# StormNet18-Remote-v0_1.net
KiCad netlist of a schematic drawn in EAGLE
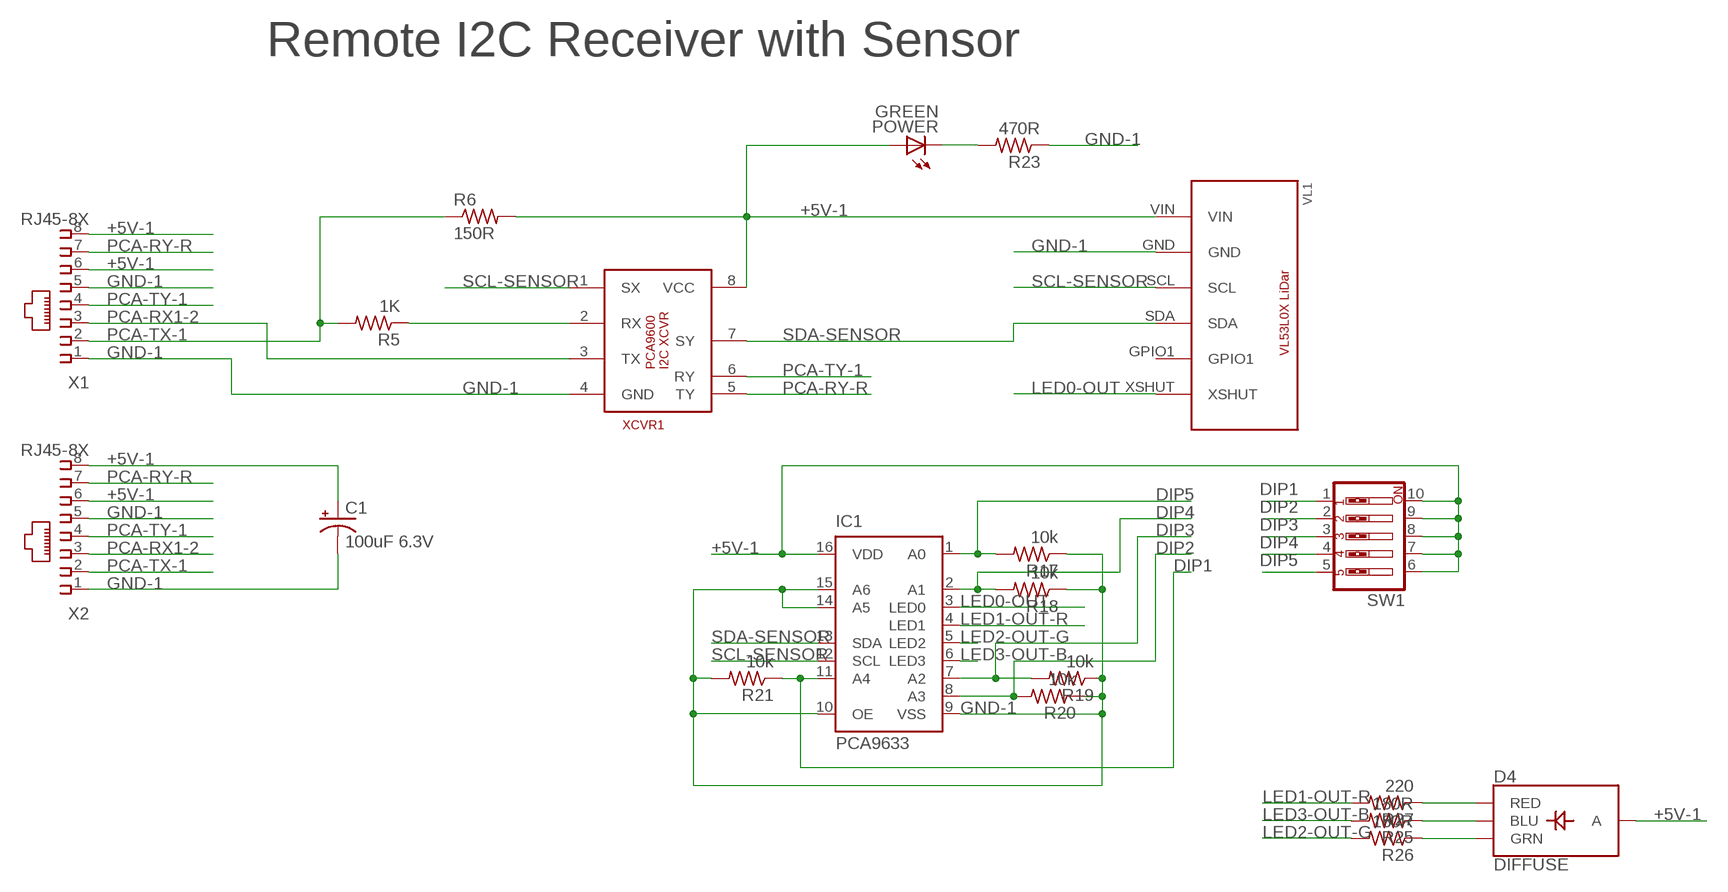
[diagram p0: schematic, sheet 1]

(export (version "E")
  (design (tool "Eeschema 10.0.6"))
  (components
    (comp (ref "C1")
      (value "100uF 6.3V")
      (footprint "eagle-import:CT3528")
      (libsource (lib "eagle-import") (part "CPOL-USCT3528"))
    )
    (comp (ref "D4")
      (value "DIFFUSE")
      (footprint "eagle-import:LED-RGB-THRU")
      (libsource (lib "eagle-import") (part "LED-RGB-CADIFFUSE"))
    )
    (comp (ref "IC1")
      (value "PCA9633")
      (footprint "eagle-import:SO16")
      (libsource (lib "eagle-import") (part "PCA9633"))
    )
    (comp (ref "POWER")
      (value "GREEN")
      (footprint "eagle-import:CHIPLED_1206")
      (libsource (lib "eagle-import") (part "LEDCHIPLED_1206"))
    )
    (comp (ref "R5")
      (value "1K")
      (footprint "eagle-import:R0603")
      (libsource (lib "eagle-import") (part "R-US_R0603"))
    )
    (comp (ref "R6")
      (value "150R")
      (footprint "eagle-import:R0603")
      (libsource (lib "eagle-import") (part "R-US_R0603"))
    )
    (comp (ref "R17")
      (value "10k")
      (footprint "eagle-import:R0603")
      (libsource (lib "eagle-import") (part "R-US_R0603"))
    )
    (comp (ref "R18")
      (value "10k")
      (footprint "eagle-import:R0603")
      (libsource (lib "eagle-import") (part "R-US_R0603"))
    )
    (comp (ref "R19")
      (value "10k")
      (footprint "eagle-import:R0603")
      (libsource (lib "eagle-import") (part "R-US_R0603"))
    )
    (comp (ref "R20")
      (value "10k")
      (footprint "eagle-import:R0603")
      (libsource (lib "eagle-import") (part "R-US_R0603"))
    )
    (comp (ref "R21")
      (value "10k")
      (footprint "eagle-import:R0603")
      (libsource (lib "eagle-import") (part "R-US_R0603"))
    )
    (comp (ref "R23")
      (value "470R")
      (footprint "eagle-import:R0603")
      (libsource (lib "eagle-import") (part "R-US_R0603"))
    )
    (comp (ref "R25")
      (value "180R")
      (footprint "eagle-import:R0603")
      (libsource (lib "eagle-import") (part "R-US_R0603"))
    )
    (comp (ref "R26")
      (value "180R")
      (footprint "eagle-import:R0603")
      (libsource (lib "eagle-import") (part "R-US_R0603"))
    )
    (comp (ref "R27")
      (value "220")
      (footprint "eagle-import:R0603")
      (libsource (lib "eagle-import") (part "R-US_R0603"))
    )
    (comp (ref "SW1")
      (value "SW_DIP-5")
      (footprint "eagle-import:EDG-05")
      (libsource (lib "eagle-import") (part "SW_DIP-5"))
    )
    (comp (ref "VL1")
      (value "VL53L0X-GREEN")
      (footprint "eagle-import:VL53L0X-GREEN")
      (libsource (lib "eagle-import") (part "VL53L0X-GREEN"))
    )
    (comp (ref "X1")
      (value "RJ45-8X")
      (footprint "eagle-import:RJ45-NO-SHIELD")
      (libsource (lib "eagle-import") (part "RJ45-8X"))
    )
    (comp (ref "X2")
      (value "RJ45-8X")
      (footprint "eagle-import:RJ45-NO-SHIELD")
      (libsource (lib "eagle-import") (part "RJ45-8X"))
    )
    (comp (ref "XCVR1")
      (value "PCA9600DSO8")
      (footprint "eagle-import:SO08")
      (libsource (lib "eagle-import") (part "PCA9600DSO8"))
    )
  )
  (nets
    (net (code "1") (name "/+5V-1") (class "Default")
      (node (ref "C1") (pin "+") (pinfunction "+_+") (pintype "passive"))
      (node (ref "D4") (pin "2") (pinfunction "A_2") (pintype "bidirectional"))
      (node (ref "IC1") (pin "16") (pinfunction "VDD_16") (pintype "power_in"))
      (node (ref "POWER") (pin "A") (pinfunction "A_A") (pintype "passive"))
      (node (ref "R6") (pin "2") (pinfunction "2_2") (pintype "passive"))
      (node (ref "SW1") (pin "10") (pinfunction "10_10") (pintype "passive"))
      (node (ref "SW1") (pin "6") (pinfunction "6_6") (pintype "passive"))
      (node (ref "SW1") (pin "7") (pinfunction "7_7") (pintype "passive"))
      (node (ref "SW1") (pin "8") (pinfunction "8_8") (pintype "passive"))
      (node (ref "SW1") (pin "9") (pinfunction "9_9") (pintype "passive"))
      (node (ref "VL1") (pin "VIN") (pinfunction "VIN_VIN") (pintype "power_in"))
      (node (ref "X1") (pin "6") (pinfunction "6_6") (pintype "passive"))
      (node (ref "X1") (pin "8") (pinfunction "8_8") (pintype "passive"))
      (node (ref "X2") (pin "6") (pinfunction "6_6") (pintype "passive"))
      (node (ref "X2") (pin "8") (pinfunction "8_8") (pintype "passive"))
      (node (ref "XCVR1") (pin "8") (pinfunction "VCC_8") (pintype "bidirectional"))
    )
    (net (code "2") (name "/DIP1") (class "Default")
      (node (ref "IC1") (pin "11") (pinfunction "A4_11") (pintype "input"))
      (node (ref "R21") (pin "1") (pinfunction "1_1") (pintype "passive"))
      (node (ref "SW1") (pin "1") (pinfunction "1_1") (pintype "passive"))
    )
    (net (code "3") (name "/DIP2") (class "Default")
      (node (ref "IC1") (pin "8") (pinfunction "A3_8") (pintype "bidirectional"))
      (node (ref "R20") (pin "2") (pinfunction "2_2") (pintype "passive"))
      (node (ref "SW1") (pin "2") (pinfunction "2_2") (pintype "passive"))
    )
    (net (code "4") (name "/DIP3") (class "Default")
      (node (ref "IC1") (pin "7") (pinfunction "A2_7") (pintype "bidirectional"))
      (node (ref "R19") (pin "2") (pinfunction "2_2") (pintype "passive"))
      (node (ref "SW1") (pin "3") (pinfunction "3_3") (pintype "passive"))
    )
    (net (code "5") (name "/DIP4") (class "Default")
      (node (ref "IC1") (pin "2") (pinfunction "A1_2") (pintype "bidirectional"))
      (node (ref "R18") (pin "2") (pinfunction "2_2") (pintype "passive"))
      (node (ref "SW1") (pin "4") (pinfunction "4_4") (pintype "passive"))
    )
    (net (code "6") (name "/DIP5") (class "Default")
      (node (ref "IC1") (pin "1") (pinfunction "A0_1") (pintype "open_collector"))
      (node (ref "R17") (pin "2") (pinfunction "2_2") (pintype "passive"))
      (node (ref "SW1") (pin "5") (pinfunction "5_5") (pintype "passive"))
    )
    (net (code "7") (name "/GND-1") (class "Default")
      (node (ref "C1") (pin "-") (pinfunction "-_-") (pintype "passive"))
      (node (ref "IC1") (pin "10") (pinfunction "OE_10") (pintype "power_in"))
      (node (ref "IC1") (pin "14") (pinfunction "A5_14") (pintype "bidirectional"))
      (node (ref "IC1") (pin "15") (pinfunction "A6_15") (pintype "input"))
      (node (ref "IC1") (pin "9") (pinfunction "VSS_9") (pintype "bidirectional"))
      (node (ref "R17") (pin "1") (pinfunction "1_1") (pintype "passive"))
      (node (ref "R18") (pin "1") (pinfunction "1_1") (pintype "passive"))
      (node (ref "R19") (pin "1") (pinfunction "1_1") (pintype "passive"))
      (node (ref "R20") (pin "1") (pinfunction "1_1") (pintype "passive"))
      (node (ref "R21") (pin "2") (pinfunction "2_2") (pintype "passive"))
      (node (ref "R23") (pin "1") (pinfunction "1_1") (pintype "passive"))
      (node (ref "VL1") (pin "GND") (pinfunction "GND_GND") (pintype "power_in"))
      (node (ref "X1") (pin "1") (pinfunction "1_1") (pintype "passive"))
      (node (ref "X1") (pin "5") (pinfunction "5_5") (pintype "passive"))
      (node (ref "X2") (pin "1") (pinfunction "1_1") (pintype "passive"))
      (node (ref "X2") (pin "5") (pinfunction "5_5") (pintype "passive"))
      (node (ref "XCVR1") (pin "4") (pinfunction "GND_4") (pintype "bidirectional"))
    )
    (net (code "8") (name "/LED0-OUT") (class "Default")
      (node (ref "IC1") (pin "3") (pinfunction "LED0_3") (pintype "bidirectional"))
      (node (ref "VL1") (pin "XSHUT") (pinfunction "XSHUT_XSHUT") (pintype "input"))
    )
    (net (code "9") (name "/LED1-OUT-R") (class "Default")
      (node (ref "IC1") (pin "4") (pinfunction "LED1_4") (pintype "bidirectional"))
      (node (ref "R27") (pin "2") (pinfunction "2_2") (pintype "passive"))
    )
    (net (code "10") (name "/LED2-OUT-G") (class "Default")
      (node (ref "IC1") (pin "5") (pinfunction "LED2_5") (pintype "bidirectional"))
      (node (ref "R26") (pin "2") (pinfunction "2_2") (pintype "passive"))
    )
    (net (code "11") (name "/LED3-OUT-B") (class "Default")
      (node (ref "IC1") (pin "6") (pinfunction "LED3_6") (pintype "bidirectional"))
      (node (ref "R25") (pin "2") (pinfunction "2_2") (pintype "passive"))
    )
    (net (code "12") (name "/PCA-RX1-2") (class "Default")
      (node (ref "X1") (pin "3") (pinfunction "3_3") (pintype "passive"))
      (node (ref "X2") (pin "3") (pinfunction "3_3") (pintype "passive"))
      (node (ref "XCVR1") (pin "3") (pinfunction "TX_3") (pintype "bidirectional"))
    )
    (net (code "13") (name "/PCA-RY-R") (class "Default")
      (node (ref "X1") (pin "7") (pinfunction "7_7") (pintype "passive"))
      (node (ref "X2") (pin "7") (pinfunction "7_7") (pintype "passive"))
      (node (ref "XCVR1") (pin "5") (pinfunction "TY_5") (pintype "bidirectional"))
    )
    (net (code "14") (name "/PCA-TX-1") (class "Default")
      (node (ref "R5") (pin "2") (pinfunction "2_2") (pintype "passive"))
      (node (ref "R6") (pin "1") (pinfunction "1_1") (pintype "passive"))
      (node (ref "X1") (pin "2") (pinfunction "2_2") (pintype "passive"))
      (node (ref "X2") (pin "2") (pinfunction "2_2") (pintype "passive"))
    )
    (net (code "15") (name "/PCA-TY-1") (class "Default")
      (node (ref "X1") (pin "4") (pinfunction "4_4") (pintype "passive"))
      (node (ref "X2") (pin "4") (pinfunction "4_4") (pintype "passive"))
      (node (ref "XCVR1") (pin "6") (pinfunction "RY_6") (pintype "bidirectional"))
    )
    (net (code "16") (name "/SCL-SENSOR") (class "Default")
      (node (ref "IC1") (pin "12") (pinfunction "SCL_12") (pintype "input"))
      (node (ref "VL1") (pin "SCL") (pinfunction "SCL_SCL") (pintype "input"))
      (node (ref "XCVR1") (pin "1") (pinfunction "SX_1") (pintype "bidirectional"))
    )
    (net (code "17") (name "/SDA-SENSOR") (class "Default")
      (node (ref "IC1") (pin "13") (pinfunction "SDA_13") (pintype "input"))
      (node (ref "VL1") (pin "SDA") (pinfunction "SDA_SDA") (pintype "input"))
      (node (ref "XCVR1") (pin "7") (pinfunction "SY_7") (pintype "bidirectional"))
    )
    (net (code "18") (name "Net-(D4-BLU)") (class "Default")
      (node (ref "D4") (pin "4") (pinfunction "BLU_4") (pintype "bidirectional"))
      (node (ref "R25") (pin "1") (pinfunction "1_1") (pintype "passive"))
    )
    (net (code "19") (name "Net-(D4-GRN)") (class "Default")
      (node (ref "D4") (pin "3") (pinfunction "GRN_3") (pintype "bidirectional"))
      (node (ref "R26") (pin "1") (pinfunction "1_1") (pintype "passive"))
    )
    (net (code "20") (name "Net-(D4-RED)") (class "Default")
      (node (ref "D4") (pin "1") (pinfunction "RED_1") (pintype "bidirectional"))
      (node (ref "R27") (pin "1") (pinfunction "1_1") (pintype "passive"))
    )
    (net (code "21") (name "Net-(POWER-PadC)") (class "Default")
      (node (ref "POWER") (pin "C") (pinfunction "C_C") (pintype "passive"))
      (node (ref "R23") (pin "2") (pinfunction "2_2") (pintype "passive"))
    )
    (net (code "22") (name "Net-(XCVR1-RX)") (class "Default")
      (node (ref "R5") (pin "1") (pinfunction "1_1") (pintype "passive"))
      (node (ref "XCVR1") (pin "2") (pinfunction "RX_2") (pintype "bidirectional"))
    )
    (net (code "23") (name "unconnected-(VL1-PadGPIO1)") (class "Default")
      (node (ref "VL1") (pin "GPIO1") (pinfunction "GPIO1_GPIO1") (pintype "output"))
    )
  )
)
